# design.net
KiCad netlist of a schematic drawn in Altium Designer
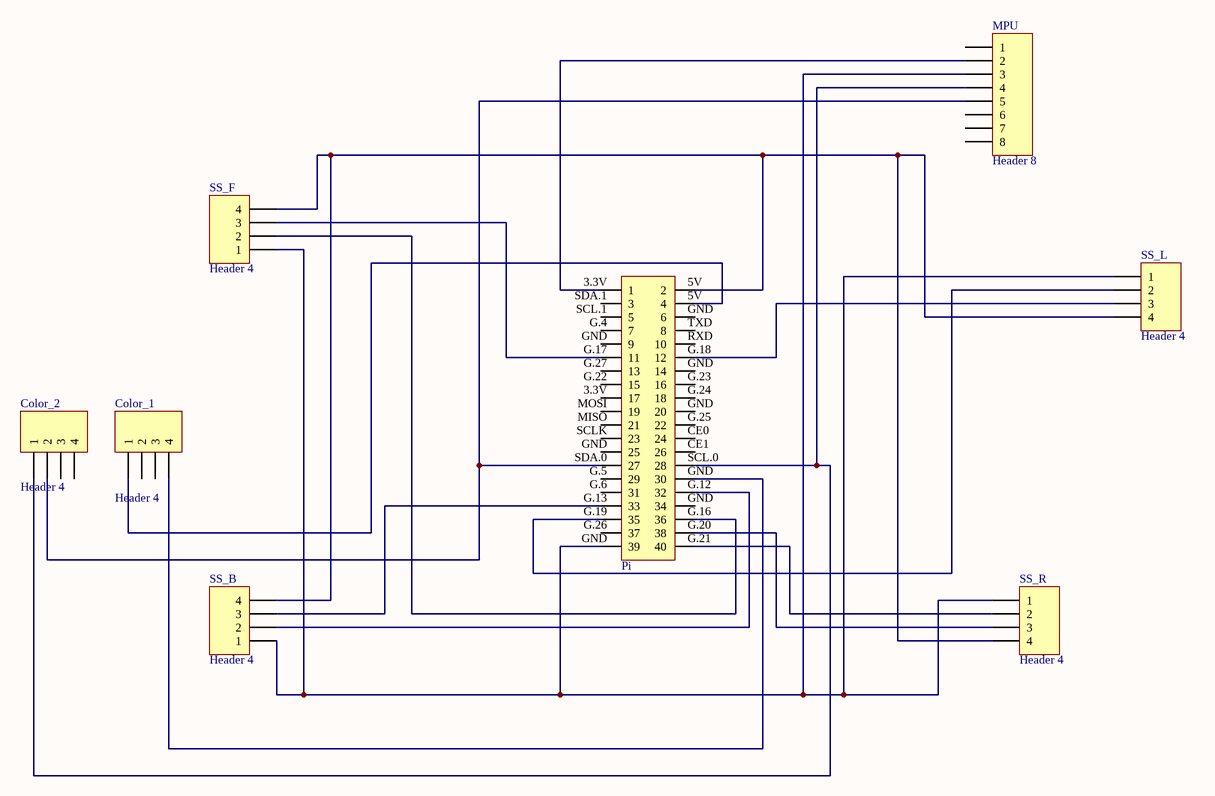
[diagram p0: 树莓派用.SchDoc]

(export (version "E")
  (design (tool "Eeschema 10.0.6"))
  (components
    (comp (ref "Color_1")
      (value "Header 4")
      (footprint "HDR1X4")
      (description "Header, 4-Pin")
      (fields (field (name "PUBLISHER") "Altium Limited"))
      (libsource (lib "") (part "Header 4_2"))
    )
    (comp (ref "Color_2")
      (value "Header 4")
      (footprint "HDR1X4")
      (description "Header, 4-Pin")
      (fields (field (name "PUBLISHER") "Altium Limited"))
      (libsource (lib "") (part "Header 4_3"))
    )
    (comp (ref "MPU")
      (value "Header 8")
      (footprint "HDR1X8")
      (description "Header, 8-Pin")
      (fields (field (name "PUBLISHER") "Altium Limited"))
      (libsource (lib "Miscellaneous Connectors") (part "Header 8"))
    )
    (comp (ref "Pi")
      (value "Header 2X11")
      (footprint "IDC2.54-LI-2x20P")
      (description "20*2P接插件")
      (fields (field (name "版权归属") "封装库来自淘宝 ID：黄晶宝石"))
      (libsource (lib "5.4 - 接插件-脚距2.54 (100mil) ") (part "Header 20X2"))
    )
    (comp (ref "SS_B")
      (value "Header 4")
      (footprint "HDR1X4")
      (description "Header, 4-Pin")
      (fields (field (name "PUBLISHER") "Altium Limited"))
      (libsource (lib "Miscellaneous Connectors") (part "Header 4"))
    )
    (comp (ref "SS_F")
      (value "Header 4")
      (footprint "HDR1X4")
      (description "Header, 4-Pin")
      (fields (field (name "PUBLISHER") "Altium Limited"))
      (libsource (lib "Miscellaneous Connectors") (part "Header 4"))
    )
    (comp (ref "SS_L")
      (value "Header 4")
      (footprint "HDR1X4")
      (description "Header, 4-Pin")
      (fields (field (name "PUBLISHER") "Altium Limited"))
      (libsource (lib "") (part "Header 4_1"))
    )
    (comp (ref "SS_R")
      (value "Header 4")
      (footprint "HDR1X4")
      (description "Header, 4-Pin")
      (fields (field (name "PUBLISHER") "Altium Limited"))
      (libsource (lib "") (part "Header 4_1"))
    )
  )
  (nets
    (net (code "1") (name "Net-(Color_1-1)") (class "Default")
      (node (ref "Color_1") (pin "VCC") (pinfunction "1_VCC") (pintype "passive"))
      (node (ref "Pi") (pin "5V") (pinfunction "4_5V") (pintype "passive"))
    )
    (net (code "2") (name "Net-(Color_1-4)") (class "Default")
      (node (ref "Color_1") (pin "GND") (pinfunction "4_GND") (pintype "passive"))
      (node (ref "Pi") (pin "GND") (pinfunction "30_GND") (pintype "passive"))
    )
    (net (code "3") (name "Net-(Color_2-1)") (class "Default")
      (node (ref "Color_2") (pin "SCL") (pinfunction "1_SCL") (pintype "passive"))
      (node (ref "MPU") (pin "SCL") (pinfunction "4_SCL") (pintype "passive"))
      (node (ref "Pi") (pin "SCL.0") (pinfunction "28_SCL.0") (pintype "passive"))
    )
    (net (code "4") (name "Net-(Color_2-2)") (class "Default")
      (node (ref "Color_2") (pin "SDA") (pinfunction "2_SDA") (pintype "passive"))
      (node (ref "MPU") (pin "SDA") (pinfunction "5_SDA") (pintype "passive"))
      (node (ref "Pi") (pin "SDA.0") (pinfunction "27_SDA.0") (pintype "passive"))
    )
    (net (code "5") (name "Net-(MPU-2)") (class "Default")
      (node (ref "MPU") (pin "3V3") (pinfunction "2_3V3") (pintype "passive"))
      (node (ref "Pi") (pin "3.3V") (pinfunction "1_3.3V") (pintype "passive"))
    )
    (net (code "6") (name "Net-(MPU-3)") (class "Default")
      (node (ref "MPU") (pin "GND") (pinfunction "3_GND") (pintype "passive"))
      (node (ref "Pi") (pin "GND") (pinfunction "39_GND") (pintype "passive"))
      (node (ref "SS_B") (pin "Gnd") (pinfunction "1_Gnd") (pintype "passive"))
      (node (ref "SS_F") (pin "Gnd") (pinfunction "1_Gnd") (pintype "passive"))
      (node (ref "SS_L") (pin "Gnd") (pinfunction "1_Gnd") (pintype "passive"))
      (node (ref "SS_R") (pin "Gnd") (pinfunction "1_Gnd") (pintype "passive"))
    )
    (net (code "7") (name "Net-(Pi-2)") (class "Default")
      (node (ref "Pi") (pin "5V") (pinfunction "2_5V") (pintype "passive"))
      (node (ref "SS_B") (pin "Vcc") (pinfunction "4_Vcc") (pintype "passive"))
      (node (ref "SS_F") (pin "Vcc") (pinfunction "4_Vcc") (pintype "passive"))
      (node (ref "SS_L") (pin "Vcc") (pinfunction "4_Vcc") (pintype "passive"))
      (node (ref "SS_R") (pin "Vcc") (pinfunction "4_Vcc") (pintype "passive"))
    )
    (net (code "8") (name "Net-(Pi-11)") (class "Default")
      (node (ref "Pi") (pin "G.17") (pinfunction "11_G.17") (pintype "passive"))
      (node (ref "SS_F") (pin "Trig") (pinfunction "3_Trig") (pintype "passive"))
    )
    (net (code "9") (name "Net-(Pi-12)") (class "Default")
      (node (ref "Pi") (pin "G.18") (pinfunction "12_G.18") (pintype "passive"))
      (node (ref "SS_L") (pin "Trig") (pinfunction "3_Trig") (pintype "passive"))
    )
    (net (code "10") (name "Net-(Pi-32)") (class "Default")
      (node (ref "Pi") (pin "G.12") (pinfunction "32_G.12") (pintype "passive"))
      (node (ref "SS_B") (pin "Echo") (pinfunction "2_Echo") (pintype "passive"))
    )
    (net (code "11") (name "Net-(Pi-33)") (class "Default")
      (node (ref "Pi") (pin "G.13") (pinfunction "33_G.13") (pintype "passive"))
      (node (ref "SS_B") (pin "Trig") (pinfunction "3_Trig") (pintype "passive"))
    )
    (net (code "12") (name "Net-(Pi-35)") (class "Default")
      (node (ref "Pi") (pin "G.19") (pinfunction "35_G.19") (pintype "passive"))
      (node (ref "SS_L") (pin "Echo") (pinfunction "2_Echo") (pintype "passive"))
    )
    (net (code "13") (name "Net-(Pi-36)") (class "Default")
      (node (ref "Pi") (pin "G.16") (pinfunction "36_G.16") (pintype "passive"))
      (node (ref "SS_F") (pin "Echo") (pinfunction "2_Echo") (pintype "passive"))
    )
    (net (code "14") (name "Net-(Pi-38)") (class "Default")
      (node (ref "Pi") (pin "G.20") (pinfunction "38_G.20") (pintype "passive"))
      (node (ref "SS_R") (pin "Trig") (pinfunction "3_Trig") (pintype "passive"))
    )
    (net (code "15") (name "Net-(Pi-40)") (class "Default")
      (node (ref "Pi") (pin "G.21") (pinfunction "40_G.21") (pintype "passive"))
      (node (ref "SS_R") (pin "Echo") (pinfunction "2_Echo") (pintype "passive"))
    )
    (net (code "16") (name "unconnected-(Color_1-2-PadCT)") (class "Default")
      (node (ref "Color_1") (pin "CT") (pinfunction "2_CT") (pintype "passive"))
    )
    (net (code "17") (name "unconnected-(Color_1-3-PadDR)") (class "Default")
      (node (ref "Color_1") (pin "DR") (pinfunction "3_DR") (pintype "passive"))
    )
    (net (code "18") (name "unconnected-(Color_2-3-PadINT)") (class "Default")
      (node (ref "Color_2") (pin "INT") (pinfunction "3_INT") (pintype "passive"))
    )
    (net (code "19") (name "unconnected-(Color_2-4-PadNC)") (class "Default")
      (node (ref "Color_2") (pin "NC") (pinfunction "4_NC") (pintype "passive"))
    )
    (net (code "20") (name "unconnected-(MPU-1-PadVCC_IN)") (class "Default")
      (node (ref "MPU") (pin "VCC_IN") (pinfunction "1_VCC_IN") (pintype "passive"))
    )
    (net (code "21") (name "unconnected-(MPU-6-PadM_DRDY)") (class "Default")
      (node (ref "MPU") (pin "M_DRDY") (pinfunction "6_M_DRDY") (pintype "passive"))
    )
    (net (code "22") (name "unconnected-(MPU-7-PadA_INTI)") (class "Default")
      (node (ref "MPU") (pin "A_INTI") (pinfunction "7_A_INTI") (pintype "passive"))
    )
    (net (code "23") (name "unconnected-(MPU-8-PadDRDY)") (class "Default")
      (node (ref "MPU") (pin "DRDY") (pinfunction "8_DRDY") (pintype "passive"))
    )
    (net (code "24") (name "unconnected-(Pi-3-PadSDA.1)") (class "Default")
      (node (ref "Pi") (pin "SDA.1") (pinfunction "3_SDA.1") (pintype "passive"))
    )
    (net (code "25") (name "unconnected-(Pi-5-PadSCL.1)") (class "Default")
      (node (ref "Pi") (pin "SCL.1") (pinfunction "5_SCL.1") (pintype "passive"))
    )
    (net (code "26") (name "unconnected-(Pi-6-PadGND)") (class "Default")
      (node (ref "Pi") (pin "GND") (pinfunction "6_GND") (pintype "passive"))
    )
    (net (code "27") (name "unconnected-(Pi-7-PadG.4)") (class "Default")
      (node (ref "Pi") (pin "G.4") (pinfunction "7_G.4") (pintype "passive"))
    )
    (net (code "28") (name "unconnected-(Pi-8-PadTXD)") (class "Default")
      (node (ref "Pi") (pin "TXD") (pinfunction "8_TXD") (pintype "passive"))
    )
    (net (code "29") (name "unconnected-(Pi-9-PadGND)") (class "Default")
      (node (ref "Pi") (pin "GND") (pinfunction "9_GND") (pintype "passive"))
    )
    (net (code "30") (name "unconnected-(Pi-10-PadRXD)") (class "Default")
      (node (ref "Pi") (pin "RXD") (pinfunction "10_RXD") (pintype "passive"))
    )
    (net (code "31") (name "unconnected-(Pi-13-PadG.27)") (class "Default")
      (node (ref "Pi") (pin "G.27") (pinfunction "13_G.27") (pintype "passive"))
    )
    (net (code "32") (name "unconnected-(Pi-14-PadGND)") (class "Default")
      (node (ref "Pi") (pin "GND") (pinfunction "14_GND") (pintype "passive"))
    )
    (net (code "33") (name "unconnected-(Pi-15-PadG.22)") (class "Default")
      (node (ref "Pi") (pin "G.22") (pinfunction "15_G.22") (pintype "passive"))
    )
    (net (code "34") (name "unconnected-(Pi-16-PadG.23)") (class "Default")
      (node (ref "Pi") (pin "G.23") (pinfunction "16_G.23") (pintype "passive"))
    )
    (net (code "35") (name "unconnected-(Pi-17-Pad3.3V)") (class "Default")
      (node (ref "Pi") (pin "3.3V") (pinfunction "17_3.3V") (pintype "passive"))
    )
    (net (code "36") (name "unconnected-(Pi-18-PadG.24)") (class "Default")
      (node (ref "Pi") (pin "G.24") (pinfunction "18_G.24") (pintype "passive"))
    )
    (net (code "37") (name "unconnected-(Pi-19-PadMOSI)") (class "Default")
      (node (ref "Pi") (pin "MOSI") (pinfunction "19_MOSI") (pintype "passive"))
    )
    (net (code "38") (name "unconnected-(Pi-20-PadGND)") (class "Default")
      (node (ref "Pi") (pin "GND") (pinfunction "20_GND") (pintype "passive"))
    )
    (net (code "39") (name "unconnected-(Pi-21-PadMISO)") (class "Default")
      (node (ref "Pi") (pin "MISO") (pinfunction "21_MISO") (pintype "passive"))
    )
    (net (code "40") (name "unconnected-(Pi-22-PadG.25)") (class "Default")
      (node (ref "Pi") (pin "G.25") (pinfunction "22_G.25") (pintype "passive"))
    )
    (net (code "41") (name "unconnected-(Pi-23-PadSCLK)") (class "Default")
      (node (ref "Pi") (pin "SCLK") (pinfunction "23_SCLK") (pintype "passive"))
    )
    (net (code "42") (name "unconnected-(Pi-24-PadCE0)") (class "Default")
      (node (ref "Pi") (pin "CE0") (pinfunction "24_CE0") (pintype "passive"))
    )
    (net (code "43") (name "unconnected-(Pi-25-PadGND)") (class "Default")
      (node (ref "Pi") (pin "GND") (pinfunction "25_GND") (pintype "passive"))
    )
    (net (code "44") (name "unconnected-(Pi-26-PadCE1)") (class "Default")
      (node (ref "Pi") (pin "CE1") (pinfunction "26_CE1") (pintype "passive"))
    )
    (net (code "45") (name "unconnected-(Pi-29-PadG.5)") (class "Default")
      (node (ref "Pi") (pin "G.5") (pinfunction "29_G.5") (pintype "passive"))
    )
    (net (code "46") (name "unconnected-(Pi-31-PadG.6)") (class "Default")
      (node (ref "Pi") (pin "G.6") (pinfunction "31_G.6") (pintype "passive"))
    )
    (net (code "47") (name "unconnected-(Pi-34-PadGND)") (class "Default")
      (node (ref "Pi") (pin "GND") (pinfunction "34_GND") (pintype "passive"))
    )
    (net (code "48") (name "unconnected-(Pi-37-PadG.26)") (class "Default")
      (node (ref "Pi") (pin "G.26") (pinfunction "37_G.26") (pintype "passive"))
    )
  )
)
